# CANBed_M0.net
KiCad netlist of a schematic drawn in EAGLE
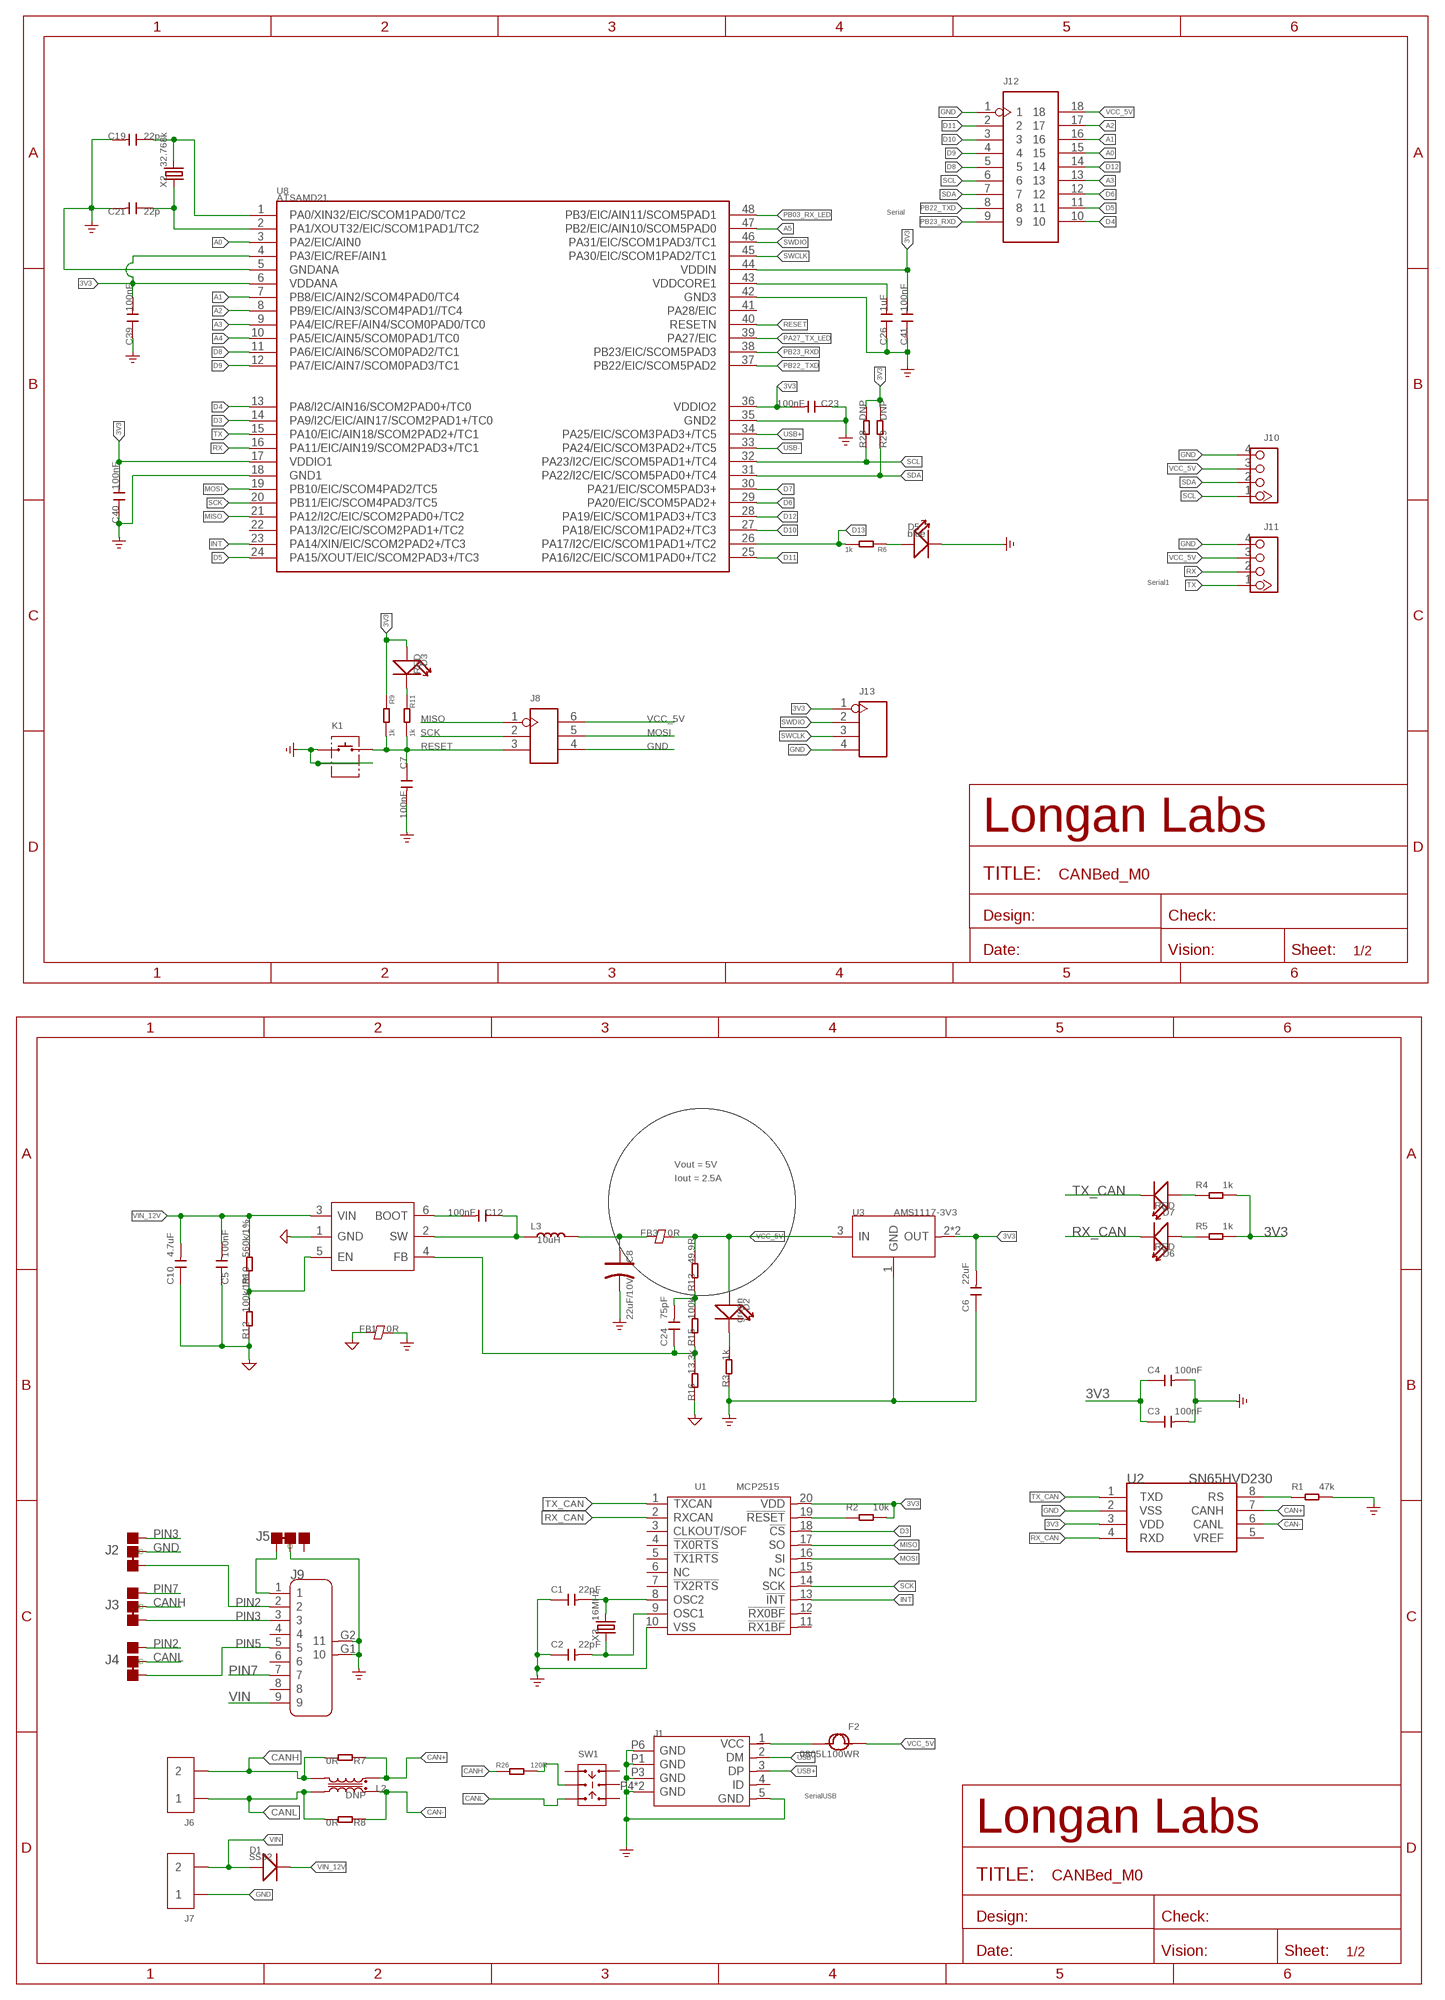
[diagram p0: schematic, sheet 1]

(export (version "E")
  (design (tool "Eeschema 10.0.6"))
  (components
    (comp (ref "C1")
      (value "22pF")
      (footprint "eagle-import:C0603")
      (libsource (lib "eagle-import") (part "CAP-0603"))
    )
    (comp (ref "C2")
      (value "22pF")
      (footprint "eagle-import:C0603")
      (libsource (lib "eagle-import") (part "CAP-0603"))
    )
    (comp (ref "C3")
      (value "100nF")
      (footprint "eagle-import:C0603")
      (libsource (lib "eagle-import") (part "CAP-0603"))
    )
    (comp (ref "C4")
      (value "100nF")
      (footprint "eagle-import:C0603")
      (libsource (lib "eagle-import") (part "CAP-0603"))
    )
    (comp (ref "C5")
      (value "100nF")
      (footprint "eagle-import:C0603")
      (libsource (lib "eagle-import") (part "CAP-0603"))
    )
    (comp (ref "C6")
      (value "22uF")
      (footprint "eagle-import:C1206")
      (libsource (lib "eagle-import") (part "CAP-1206"))
    )
    (comp (ref "C7")
      (value "100nF")
      (footprint "eagle-import:C0603")
      (libsource (lib "eagle-import") (part "CAP-0603"))
    )
    (comp (ref "C8")
      (value "22uF/10V")
      (footprint "eagle-import:AVX-B")
      (libsource (lib "eagle-import") (part "CAP-POLAR-AVX-B"))
    )
    (comp (ref "C10")
      (value "4.7uF")
      (footprint "eagle-import:C1206")
      (libsource (lib "eagle-import") (part "CAP-1206"))
    )
    (comp (ref "C12")
      (value "100nF")
      (footprint "eagle-import:C0603")
      (libsource (lib "eagle-import") (part "CAP-0603"))
    )
    (comp (ref "C19")
      (value "22p")
      (footprint "eagle-import:C0603")
      (libsource (lib "eagle-import") (part "CAP-0603"))
    )
    (comp (ref "C21")
      (value "22p")
      (footprint "eagle-import:C0603")
      (libsource (lib "eagle-import") (part "CAP-0603"))
    )
    (comp (ref "C23")
      (value "100nF")
      (footprint "eagle-import:C0603")
      (libsource (lib "eagle-import") (part "CAP-0603"))
    )
    (comp (ref "C24")
      (value "75pF")
      (footprint "eagle-import:C0603")
      (libsource (lib "eagle-import") (part "CAP-0603"))
    )
    (comp (ref "C26")
      (value "1uF")
      (footprint "eagle-import:C0603")
      (libsource (lib "eagle-import") (part "CAP-0603"))
    )
    (comp (ref "C39")
      (value "100nF")
      (footprint "eagle-import:C0603")
      (libsource (lib "eagle-import") (part "CAP-0603"))
    )
    (comp (ref "C40")
      (value "100nF")
      (footprint "eagle-import:C0603")
      (libsource (lib "eagle-import") (part "CAP-0603"))
    )
    (comp (ref "C41")
      (value "100nF")
      (footprint "eagle-import:C0603")
      (libsource (lib "eagle-import") (part "CAP-0603"))
    )
    (comp (ref "D1")
      (value "SS32")
      (footprint "eagle-import:DO-214AC")
      (libsource (lib "eagle-import") (part "DIODE'SMA'"))
    )
    (comp (ref "D2")
      (value "green")
      (footprint "eagle-import:LED-0603")
      (libsource (lib "eagle-import") (part "LED'0603'"))
    )
    (comp (ref "D3")
      (value "RED")
      (footprint "eagle-import:LED-0603")
      (libsource (lib "eagle-import") (part "LED'0603'"))
    )
    (comp (ref "D5")
      (value "blue")
      (footprint "eagle-import:LED-0603")
      (libsource (lib "eagle-import") (part "LED'0603'"))
    )
    (comp (ref "D6")
      (value "RED")
      (footprint "eagle-import:LED-0603")
      (libsource (lib "eagle-import") (part "LED'0603'"))
    )
    (comp (ref "D7")
      (value "RED")
      (footprint "eagle-import:LED-0603")
      (libsource (lib "eagle-import") (part "LED'0603'"))
    )
    (comp (ref "F2")
      (value "0805L100WR")
      (footprint "eagle-import:F0805")
      (libsource (lib "eagle-import") (part "FUSE0805"))
    )
    (comp (ref "FB1")
      (value "0R")
      (footprint "eagle-import:F0805")
      (libsource (lib "eagle-import") (part "FERRITE-BEAD-0805"))
    )
    (comp (ref "FB3")
      (value "0R")
      (footprint "eagle-import:F0805")
      (libsource (lib "eagle-import") (part "FERRITE-BEAD-0805"))
    )
    (comp (ref "J1")
      (value "MICRO-USB5+4P-320010050")
      (footprint "eagle-import:MICRO-USB5+5P-SMD-0.65-7.2X5.06MM")
      (libsource (lib "eagle-import") (part "MICRO-USB5+4P-320010050"))
    )
    (comp (ref "J2")
      (value "JUMPER-3P-SHORT")
      (footprint "eagle-import:3P-SMD-SHORT")
      (libsource (lib "eagle-import") (part "JUMPER-3P-SHORT"))
    )
    (comp (ref "J3")
      (value "JUMPER-3P-SHORT")
      (footprint "eagle-import:3P-SMD-SHORT")
      (libsource (lib "eagle-import") (part "JUMPER-3P-SHORT"))
    )
    (comp (ref "J4")
      (value "JUMPER-3P-SHORT")
      (footprint "eagle-import:3P-SMD-SHORT")
      (libsource (lib "eagle-import") (part "JUMPER-3P-SHORT"))
    )
    (comp (ref "J5")
      (value "JUMPER-3P-SHORT")
      (footprint "eagle-import:3P-SMD-SHORT")
      (libsource (lib "eagle-import") (part "JUMPER-3P-SHORT"))
    )
    (comp (ref "J6")
      (value "SCREW-TERMINAL-2P'5.08'")
      (footprint "eagle-import:H2-5.0-10.5X8.0MM")
      (libsource (lib "eagle-import") (part "SCREW-TERMINAL-2P'5.08'"))
    )
    (comp (ref "J7")
      (value "SCREW-TERMINAL-2P'5.08'")
      (footprint "eagle-import:H2-5.0-10.5X8.0MM")
      (libsource (lib "eagle-import") (part "SCREW-TERMINAL-2P'5.08'"))
    )
    (comp (ref "J8")
      (value "HEADER-2X3P-2.54")
      (footprint "eagle-import:H2X3-2.54")
      (libsource (lib "eagle-import") (part "HEADER-2X3P-2.54"))
    )
    (comp (ref "J9")
      (value "DB9'MEAL'")
      (footprint "eagle-import:DB9-MEAL")
      (libsource (lib "eagle-import") (part "DB9'MEAL'"))
    )
    (comp (ref "J10")
      (value "320110033")
      (footprint "eagle-import:HW4-2.0")
      (libsource (lib "eagle-import") (part "GROVE-CONNECTOR-DIP-2.0"))
    )
    (comp (ref "J11")
      (value "320110033")
      (footprint "eagle-import:HW4-2.0")
      (libsource (lib "eagle-import") (part "GROVE-CONNECTOR-DIP-2.0"))
    )
    (comp (ref "J12")
      (value "HEADER-2X9P-2.54")
      (footprint "eagle-import:H2X9-2.54")
      (libsource (lib "eagle-import") (part "HEADER-2X9P-2.54"))
    )
    (comp (ref "J13")
      (value "HEADER-4P-65/35MIL")
      (footprint "eagle-import:H4-2.54")
      (libsource (lib "eagle-import") (part "HEADER-4P-65/35MIL"))
    )
    (comp (ref "K1")
      (value "BUTTON-2+2P")
      (footprint "eagle-import:SW2+2P-7.7X2.75X3.95MM")
      (libsource (lib "eagle-import") (part "BUTTON-2+2P"))
    )
    (comp (ref "L2")
      (value "DNP")
      (footprint "eagle-import:INT4-0.85-2X1.25X1.2MM")
      (libsource (lib "eagle-import") (part "INDUCTOR-COMMON-MODE-SRF2012-900YA"))
    )
    (comp (ref "L3")
      (value "10uH")
      (footprint "eagle-import:INT2-SMD-6.6X7.1X3MM")
      (libsource (lib "eagle-import") (part "INDUCTOR-6.6X7.1"))
    )
    (comp (ref "R1")
      (value "47k")
      (footprint "eagle-import:R0603")
      (libsource (lib "eagle-import") (part "RES-0603"))
    )
    (comp (ref "R2")
      (value "10k")
      (footprint "eagle-import:R0603")
      (libsource (lib "eagle-import") (part "RES-0603"))
    )
    (comp (ref "R3")
      (value "1k")
      (footprint "eagle-import:R0603")
      (libsource (lib "eagle-import") (part "RES-0603"))
    )
    (comp (ref "R4")
      (value "1k")
      (footprint "eagle-import:R0603")
      (libsource (lib "eagle-import") (part "RES-0603"))
    )
    (comp (ref "R5")
      (value "1k")
      (footprint "eagle-import:R0603")
      (libsource (lib "eagle-import") (part "RES-0603"))
    )
    (comp (ref "R6")
      (value "1k")
      (footprint "eagle-import:R0603")
      (libsource (lib "eagle-import") (part "RES-0603"))
    )
    (comp (ref "R7")
      (value "0R")
      (footprint "eagle-import:R0603")
      (libsource (lib "eagle-import") (part "RES-0603"))
    )
    (comp (ref "R8")
      (value "0R")
      (footprint "eagle-import:R0603")
      (libsource (lib "eagle-import") (part "RES-0603"))
    )
    (comp (ref "R9")
      (value "1k")
      (footprint "eagle-import:R0603")
      (libsource (lib "eagle-import") (part "RES-0603"))
    )
    (comp (ref "R10")
      (value "560k/1%")
      (footprint "eagle-import:R0603")
      (libsource (lib "eagle-import") (part "RES-0603"))
    )
    (comp (ref "R11")
      (value "1k")
      (footprint "eagle-import:R0603")
      (libsource (lib "eagle-import") (part "RES-0603"))
    )
    (comp (ref "R12")
      (value "100k/1%")
      (footprint "eagle-import:R0603")
      (libsource (lib "eagle-import") (part "RES-0603"))
    )
    (comp (ref "R13")
      (value "49.9R")
      (footprint "eagle-import:R0603")
      (libsource (lib "eagle-import") (part "RES-0603"))
    )
    (comp (ref "R15")
      (value "100k")
      (footprint "eagle-import:R0603")
      (libsource (lib "eagle-import") (part "RES-0603"))
    )
    (comp (ref "R16")
      (value "13.3k")
      (footprint "eagle-import:R0603")
      (libsource (lib "eagle-import") (part "RES-0603"))
    )
    (comp (ref "R26")
      (value "120R")
      (footprint "eagle-import:R0603")
      (libsource (lib "eagle-import") (part "RES-0603"))
    )
    (comp (ref "R28")
      (value "DNP")
      (footprint "eagle-import:R0603")
      (libsource (lib "eagle-import") (part "RES-0603"))
    )
    (comp (ref "R29")
      (value "DNP")
      (footprint "eagle-import:R0603")
      (libsource (lib "eagle-import") (part "RES-0603"))
    )
    (comp (ref "SW1")
      (value "SWITCH-2CH-6P-311010004")
      (footprint "eagle-import:SW6-2.54-9.0X3.5X3.2+2.0MM")
      (libsource (lib "eagle-import") (part "SWITCH-2CH-6P-311010004"))
    )
    (comp (ref "U1")
      (value "MCP2515")
      (footprint "eagle-import:TSSOP20-0.65-6.5X4.4MM")
      (libsource (lib "eagle-import") (part "MCP2515'ST'"))
    )
    (comp (ref "U2")
      (value "SN65HVD230")
      (footprint "eagle-import:SOIC8-6.0")
      (libsource (lib "eagle-import") (part "MCP2551-SOIC8"))
    )
    (comp (ref "U3")
      (value "AMS1117-3V3")
      (footprint "eagle-import:SOT-223")
      (libsource (lib "eagle-import") (part "PMIC-CJ1117S"))
    )
    (comp (ref "U6")
      (value "PMIC-TPS54302")
      (footprint "eagle-import:SOT-23-6")
      (libsource (lib "eagle-import") (part "PMIC-TPS54302"))
    )
    (comp (ref "U8")
      (value "ATSAMD21")
      (footprint "eagle-import:TQFP48-0.5-7X7MM")
      (libsource (lib "eagle-import") (part "MCU-ATSAMD21-TQFP48"))
    )
    (comp (ref "X2")
      (value "32.768k")
      (footprint "eagle-import:X2-SMD-3.2X1.5X0.55MM")
      (libsource (lib "eagle-import") (part "CRYSTAL-2P-3215"))
    )
    (comp (ref "X3")
      (value "16MHz")
      (footprint "eagle-import:X4-SMD-3.2X2.5X0.7MM")
      (libsource (lib "eagle-import") (part "CRYSTAL-2P-3225"))
    )
  )
  (nets
    (net (code "1") (name "3V3") (class "Default")
      (node (ref "C23") (pin "2") (pinfunction "2_2") (pintype "passive"))
      (node (ref "C3") (pin "1") (pinfunction "1_1") (pintype "passive"))
      (node (ref "C39") (pin "2") (pinfunction "2_2") (pintype "passive"))
      (node (ref "C4") (pin "1") (pinfunction "1_1") (pintype "passive"))
      (node (ref "C40") (pin "2") (pinfunction "2_2") (pintype "passive"))
      (node (ref "C41") (pin "2") (pinfunction "2_2") (pintype "passive"))
      (node (ref "C6") (pin "2") (pinfunction "2_2") (pintype "passive"))
      (node (ref "D3") (pin "+") (pinfunction "+_+") (pintype "passive"))
      (node (ref "J13") (pin "1") (pinfunction "P$1_1") (pintype "bidirectional"))
      (node (ref "R2") (pin "2") (pinfunction "2_2") (pintype "passive"))
      (node (ref "R28") (pin "2") (pinfunction "2_2") (pintype "passive"))
      (node (ref "R29") (pin "1") (pinfunction "1_1") (pintype "passive"))
      (node (ref "R4") (pin "2") (pinfunction "2_2") (pintype "passive"))
      (node (ref "R5") (pin "2") (pinfunction "2_2") (pintype "passive"))
      (node (ref "R9") (pin "1") (pinfunction "1_1") (pintype "passive"))
      (node (ref "U1") (pin "20") (pinfunction "VDD_20") (pintype "bidirectional"))
      (node (ref "U2") (pin "3") (pinfunction "VDD_3") (pintype "bidirectional"))
      (node (ref "U3") (pin "2") (pinfunction "OUT_2") (pintype "bidirectional"))
      (node (ref "U3") (pin "TER") (pinfunction "OUT_TER") (pintype "bidirectional"))
      (node (ref "U8") (pin "17") (pinfunction "VDDIO1_17") (pintype "power_in"))
      (node (ref "U8") (pin "36") (pinfunction "VDDIO2_36") (pintype "power_in"))
      (node (ref "U8") (pin "4") (pinfunction "PA3/EIC/REF/AIN1_4") (pintype "bidirectional"))
      (node (ref "U8") (pin "44") (pinfunction "VDDIN_44") (pintype "power_in"))
      (node (ref "U8") (pin "6") (pinfunction "VDDANA_6") (pintype "power_in"))
    )
    (net (code "2") (name "A0") (class "Default")
      (node (ref "J12") (pin "15") (pinfunction "15_15") (pintype "bidirectional"))
      (node (ref "U8") (pin "3") (pinfunction "PA2/EIC/AIN0_3") (pintype "bidirectional"))
    )
    (net (code "3") (name "A1") (class "Default")
      (node (ref "J12") (pin "16") (pinfunction "16_16") (pintype "bidirectional"))
      (node (ref "U8") (pin "7") (pinfunction "PB8/EIC/AIN2/SCOM4PAD0/TC4_7") (pintype "bidirectional"))
    )
    (net (code "4") (name "A2") (class "Default")
      (node (ref "J12") (pin "17") (pinfunction "17_17") (pintype "bidirectional"))
      (node (ref "U8") (pin "8") (pinfunction "PB9/EIC/AIN3/SCOM4PAD1//TC4_8") (pintype "bidirectional"))
    )
    (net (code "5") (name "A3") (class "Default")
      (node (ref "J12") (pin "13") (pinfunction "13_13") (pintype "bidirectional"))
      (node (ref "U8") (pin "9") (pinfunction "PA4/EIC/REF/AIN4/SCOM0PAD0/TC0_9") (pintype "bidirectional"))
    )
    (net (code "6") (name "A4") (class "Default")
      (node (ref "U8") (pin "10") (pinfunction "PA5/EIC/AIN5/SCOM0PAD1/TC0_10") (pintype "bidirectional"))
    )
    (net (code "7") (name "A5") (class "Default")
      (node (ref "U8") (pin "47") (pinfunction "PB2/EIC/AIN10/SCOM5PAD0_47") (pintype "bidirectional"))
    )
    (net (code "8") (name "AGND") (class "Default")
      (node (ref "C10") (pin "1") (pinfunction "1_1") (pintype "passive"))
      (node (ref "C5") (pin "1") (pinfunction "1_1") (pintype "passive"))
      (node (ref "FB1") (pin "1") (pinfunction "1_1") (pintype "bidirectional"))
      (node (ref "R12") (pin "1") (pinfunction "1_1") (pintype "passive"))
      (node (ref "R16") (pin "1") (pinfunction "1_1") (pintype "passive"))
      (node (ref "U6") (pin "1") (pinfunction "GND_1") (pintype "bidirectional"))
    )
    (net (code "9") (name "CAN+") (class "Default")
      (node (ref "L2") (pin "4") (pinfunction "4_4") (pintype "bidirectional"))
      (node (ref "R7") (pin "1") (pinfunction "1_1") (pintype "passive"))
      (node (ref "U2") (pin "7") (pinfunction "CANH_7") (pintype "bidirectional"))
    )
    (net (code "10") (name "CAN-") (class "Default")
      (node (ref "L2") (pin "1") (pinfunction "1_1") (pintype "bidirectional"))
      (node (ref "R8") (pin "1") (pinfunction "1_1") (pintype "passive"))
      (node (ref "U2") (pin "6") (pinfunction "CANL_6") (pintype "bidirectional"))
    )
    (net (code "11") (name "CANH") (class "Default")
      (node (ref "J3") (pin "MM") (pinfunction "C_MM") (pintype "bidirectional"))
      (node (ref "J6") (pin "2") (pinfunction "2_2") (pintype "bidirectional"))
      (node (ref "L2") (pin "3") (pinfunction "3_3") (pintype "bidirectional"))
      (node (ref "R26") (pin "1") (pinfunction "1_1") (pintype "passive"))
      (node (ref "R7") (pin "2") (pinfunction "2_2") (pintype "passive"))
    )
    (net (code "12") (name "CANL") (class "Default")
      (node (ref "J4") (pin "MM") (pinfunction "C_MM") (pintype "bidirectional"))
      (node (ref "J6") (pin "1") (pinfunction "1_1") (pintype "bidirectional"))
      (node (ref "L2") (pin "2") (pinfunction "2_2") (pintype "bidirectional"))
      (node (ref "R8") (pin "2") (pinfunction "2_2") (pintype "passive"))
      (node (ref "SW1") (pin "CH1B") (pinfunction "CH1B_CH1B") (pintype "bidirectional"))
    )
    (net (code "13") (name "D3") (class "Default")
      (node (ref "U1") (pin "18") (pinfunction "~{CS}_18") (pintype "bidirectional"))
      (node (ref "U8") (pin "14") (pinfunction "PA9/I2C/EIC/AIN17/SCOM2PAD1+/TC0_14") (pintype "bidirectional"))
    )
    (net (code "14") (name "D4") (class "Default")
      (node (ref "J12") (pin "10") (pinfunction "10_10") (pintype "bidirectional"))
      (node (ref "U8") (pin "13") (pinfunction "PA8/I2C/AIN16/SCOM2PAD0+/TC0_13") (pintype "bidirectional"))
    )
    (net (code "15") (name "D5") (class "Default")
      (node (ref "J12") (pin "11") (pinfunction "11_11") (pintype "bidirectional"))
      (node (ref "U8") (pin "24") (pinfunction "PA15/XOUT/EIC/SCOM2PAD3+/TC3_24") (pintype "bidirectional"))
    )
    (net (code "16") (name "D6") (class "Default")
      (node (ref "J12") (pin "12") (pinfunction "12_12") (pintype "bidirectional"))
      (node (ref "U8") (pin "29") (pinfunction "PA20/EIC/SCOM5PAD2+_29") (pintype "bidirectional"))
    )
    (net (code "17") (name "D7") (class "Default")
      (node (ref "U8") (pin "30") (pinfunction "PA21/EIC/SCOM5PAD3+_30") (pintype "bidirectional"))
    )
    (net (code "18") (name "D8") (class "Default")
      (node (ref "J12") (pin "5") (pinfunction "5_5") (pintype "bidirectional"))
      (node (ref "U8") (pin "11") (pinfunction "PA6/EIC/AIN6/SCOM0PAD2/TC1_11") (pintype "bidirectional"))
    )
    (net (code "19") (name "D9") (class "Default")
      (node (ref "J12") (pin "4") (pinfunction "4_4") (pintype "bidirectional"))
      (node (ref "U8") (pin "12") (pinfunction "PA7/EIC/AIN7/SCOM0PAD3/TC1_12") (pintype "bidirectional"))
    )
    (net (code "20") (name "D10") (class "Default")
      (node (ref "J12") (pin "3") (pinfunction "3_3") (pintype "bidirectional"))
      (node (ref "U8") (pin "27") (pinfunction "PA18/EIC/SCOM1PAD2+/TC3_27") (pintype "bidirectional"))
    )
    (net (code "21") (name "D11") (class "Default")
      (node (ref "J12") (pin "2") (pinfunction "2_2") (pintype "bidirectional"))
      (node (ref "U8") (pin "25") (pinfunction "PA16/I2C/EIC/SCOM1PAD0+/TC2_25") (pintype "bidirectional"))
    )
    (net (code "22") (name "D12") (class "Default")
      (node (ref "J12") (pin "14") (pinfunction "14_14") (pintype "bidirectional"))
      (node (ref "U8") (pin "28") (pinfunction "PA19/EIC/SCOM1PAD3+/TC3_28") (pintype "bidirectional"))
    )
    (net (code "23") (name "D13") (class "Default")
      (node (ref "R6") (pin "2") (pinfunction "2_2") (pintype "passive"))
      (node (ref "U8") (pin "26") (pinfunction "PA17/I2C/EIC/SCOM1PAD1+/TC2_26") (pintype "bidirectional"))
    )
    (net (code "24") (name "GND") (class "Default")
      (node (ref "C1") (pin "1") (pinfunction "1_1") (pintype "passive"))
      (node (ref "C19") (pin "2") (pinfunction "2_2") (pintype "passive"))
      (node (ref "C2") (pin "1") (pinfunction "1_1") (pintype "passive"))
      (node (ref "C21") (pin "2") (pinfunction "2_2") (pintype "passive"))
      (node (ref "C23") (pin "1") (pinfunction "1_1") (pintype "passive"))
      (node (ref "C26") (pin "1") (pinfunction "1_1") (pintype "passive"))
      (node (ref "C3") (pin "2") (pinfunction "2_2") (pintype "passive"))
      (node (ref "C39") (pin "1") (pinfunction "1_1") (pintype "passive"))
      (node (ref "C4") (pin "2") (pinfunction "2_2") (pintype "passive"))
      (node (ref "C40") (pin "1") (pinfunction "1_1") (pintype "passive"))
      (node (ref "C41") (pin "1") (pinfunction "1_1") (pintype "passive"))
      (node (ref "C6") (pin "1") (pinfunction "1_1") (pintype "passive"))
      (node (ref "C7") (pin "2") (pinfunction "2_2") (pintype "passive"))
      (node (ref "C8") (pin "-") (pinfunction "-_-") (pintype "passive"))
      (node (ref "D5") (pin "-") (pinfunction "-_-") (pintype "passive"))
      (node (ref "FB1") (pin "2") (pinfunction "2_2") (pintype "bidirectional"))
      (node (ref "J1") (pin "5") (pinfunction "GND_5") (pintype "bidirectional"))
      (node (ref "J1") (pin "P1") (pinfunction "GND_P1") (pintype "bidirectional"))
      (node (ref "J1") (pin "P3") (pinfunction "GND_P3") (pintype "bidirectional"))
      (node (ref "J1") (pin "P4") (pinfunction "GND_P4") (pintype "bidirectional"))
      (node (ref "J1") (pin "P5") (pinfunction "GND_P5") (pintype "bidirectional"))
      (node (ref "J1") (pin "P6") (pinfunction "GND_P6") (pintype "bidirectional"))
      (node (ref "J10") (pin "4") (pinfunction "4_4") (pintype "bidirectional"))
      (node (ref "J11") (pin "4") (pinfunction "4_4") (pintype "bidirectional"))
      (node (ref "J12") (pin "1") (pinfunction "1_1") (pintype "bidirectional"))
      (node (ref "J13") (pin "4") (pinfunction "P$4_4") (pintype "bidirectional"))
      (node (ref "J2") (pin "MM") (pinfunction "C_MM") (pintype "bidirectional"))
      (node (ref "J5") (pin "MM") (pinfunction "C_MM") (pintype "bidirectional"))
      (node (ref "J7") (pin "1") (pinfunction "1_1") (pintype "bidirectional"))
      (node (ref "J8") (pin "4") (pinfunction "4_4") (pintype "bidirectional"))
      (node (ref "J9") (pin "G1") (pinfunction "10_G1") (pintype "bidirectional"))
      (node (ref "J9") (pin "G2") (pinfunction "11_G2") (pintype "bidirectional"))
      (node (ref "K1") (pin "1") (pinfunction "1_1") (pintype "bidirectional"))
      (node (ref "K1") (pin "S1") (pinfunction "S1_S1") (pintype "bidirectional"))
      (node (ref "K1") (pin "S2") (pinfunction "S2_S2") (pintype "bidirectional"))
      (node (ref "R1") (pin "2") (pinfunction "2_2") (pintype "passive"))
      (node (ref "R3") (pin "1") (pinfunction "1_1") (pintype "passive"))
      (node (ref "U1") (pin "10") (pinfunction "VSS_10") (pintype "bidirectional"))
      (node (ref "U2") (pin "2") (pinfunction "VSS_2") (pintype "bidirectional"))
      (node (ref "U3") (pin "1") (pinfunction "GND_1") (pintype "bidirectional"))
      (node (ref "U8") (pin "18") (pinfunction "GND1_18") (pintype "power_in"))
      (node (ref "U8") (pin "35") (pinfunction "GND2_35") (pintype "power_in"))
      (node (ref "U8") (pin "42") (pinfunction "GND3_42") (pintype "power_in"))
      (node (ref "U8") (pin "5") (pinfunction "GNDANA_5") (pintype "power_in"))
    )
    (net (code "25") (name "INT") (class "Default")
      (node (ref "U1") (pin "13") (pinfunction "~{INT}_13") (pintype "bidirectional"))
      (node (ref "U8") (pin "23") (pinfunction "PA14/XIN/EIC/SCOM2PAD2+/TC3_23") (pintype "bidirectional"))
    )
    (net (code "26") (name "MISO") (class "Default")
      (node (ref "J8") (pin "1") (pinfunction "1_1") (pintype "bidirectional"))
      (node (ref "U1") (pin "17") (pinfunction "SO_17") (pintype "bidirectional"))
      (node (ref "U8") (pin "21") (pinfunction "PA12/I2C/EIC/SCOM2PAD0+/TC2_21") (pintype "bidirectional"))
    )
    (net (code "27") (name "MOSI") (class "Default")
      (node (ref "J8") (pin "5") (pinfunction "5_5") (pintype "bidirectional"))
      (node (ref "U1") (pin "16") (pinfunction "SI_16") (pintype "bidirectional"))
      (node (ref "U8") (pin "19") (pinfunction "PB10/EIC/SCOM4PAD2/TC5_19") (pintype "bidirectional"))
    )
    (net (code "28") (name "Net-(C8-Pad+)") (class "Default")
      (node (ref "C8") (pin "+") (pinfunction "+_+") (pintype "passive"))
      (node (ref "FB3") (pin "1") (pinfunction "1_1") (pintype "bidirectional"))
      (node (ref "L3") (pin "2") (pinfunction "2_2") (pintype "passive"))
    )
    (net (code "29") (name "Net-(C24-Pad2)") (class "Default")
      (node (ref "C24") (pin "2") (pinfunction "2_2") (pintype "passive"))
      (node (ref "R13") (pin "1") (pinfunction "1_1") (pintype "passive"))
      (node (ref "R15") (pin "2") (pinfunction "2_2") (pintype "passive"))
    )
    (net (code "30") (name "Net-(D2-Pad-)") (class "Default")
      (node (ref "D2") (pin "-") (pinfunction "-_-") (pintype "passive"))
      (node (ref "R3") (pin "2") (pinfunction "2_2") (pintype "passive"))
    )
    (net (code "31") (name "Net-(D3-Pad-)") (class "Default")
      (node (ref "D3") (pin "-") (pinfunction "-_-") (pintype "passive"))
      (node (ref "R11") (pin "1") (pinfunction "1_1") (pintype "passive"))
    )
    (net (code "32") (name "Net-(D5-Pad+)") (class "Default")
      (node (ref "D5") (pin "+") (pinfunction "+_+") (pintype "passive"))
      (node (ref "R6") (pin "1") (pinfunction "1_1") (pintype "passive"))
    )
    (net (code "33") (name "Net-(D6-Pad+)") (class "Default")
      (node (ref "D6") (pin "+") (pinfunction "+_+") (pintype "passive"))
      (node (ref "R5") (pin "1") (pinfunction "1_1") (pintype "passive"))
    )
    (net (code "34") (name "Net-(D7-Pad+)") (class "Default")
      (node (ref "D7") (pin "+") (pinfunction "+_+") (pintype "passive"))
      (node (ref "R4") (pin "1") (pinfunction "1_1") (pintype "passive"))
    )
    (net (code "35") (name "Net-(J1-VCC)") (class "Default")
      (node (ref "F2") (pin "2") (pinfunction "2_2") (pintype "bidirectional"))
      (node (ref "J1") (pin "1") (pinfunction "VCC_1") (pintype "bidirectional"))
    )
    (net (code "36") (name "Net-(J5-L)") (class "Default")
      (node (ref "J5") (pin "11") (pinfunction "L_11") (pintype "bidirectional"))
      (node (ref "J9") (pin "1") (pinfunction "1_1") (pintype "bidirectional"))
    )
    (net (code "37") (name "Net-(R26-Pad2)") (class "Default")
      (node (ref "R26") (pin "2") (pinfunction "2_2") (pintype "passive"))
      (node (ref "SW1") (pin "COM1") (pinfunction "COM1_COM1") (pintype "bidirectional"))
    )
    (net (code "38") (name "Net-(U1-OSC1)") (class "Default")
      (node (ref "C2") (pin "2") (pinfunction "2_2") (pintype "passive"))
      (node (ref "U1") (pin "9") (pinfunction "OSC1_9") (pintype "bidirectional"))
      (node (ref "X3") (pin "1") (pinfunction "1_1") (pintype "passive"))
    )
    (net (code "39") (name "Net-(U1-OSC2)") (class "Default")
      (node (ref "C1") (pin "2") (pinfunction "2_2") (pintype "passive"))
      (node (ref "U1") (pin "8") (pinfunction "OSC2_8") (pintype "bidirectional"))
      (node (ref "X3") (pin "3") (pinfunction "2_3") (pintype "passive"))
    )
    (net (code "40") (name "Net-(U1-~{RESET})") (class "Default")
      (node (ref "R2") (pin "1") (pinfunction "1_1") (pintype "passive"))
      (node (ref "U1") (pin "19") (pinfunction "~{RESET}_19") (pintype "bidirectional"))
    )
    (net (code "41") (name "Net-(U2-RS)") (class "Default")
      (node (ref "R1") (pin "1") (pinfunction "1_1") (pintype "passive"))
      (node (ref "U2") (pin "8") (pinfunction "RS_8") (pintype "bidirectional"))
    )
    (net (code "42") (name "Net-(U6-BOOT)") (class "Default")
      (node (ref "C12") (pin "2") (pinfunction "2_2") (pintype "passive"))
      (node (ref "U6") (pin "6") (pinfunction "BOOT_6") (pintype "bidirectional"))
    )
    (net (code "43") (name "Net-(U6-EN)") (class "Default")
      (node (ref "R10") (pin "1") (pinfunction "1_1") (pintype "passive"))
      (node (ref "R12") (pin "2") (pinfunction "2_2") (pintype "passive"))
      (node (ref "U6") (pin "5") (pinfunction "EN_5") (pintype "bidirectional"))
    )
    (net (code "44") (name "Net-(U6-FB)") (class "Default")
      (node (ref "C24") (pin "1") (pinfunction "1_1") (pintype "passive"))
      (node (ref "R15") (pin "1") (pinfunction "1_1") (pintype "passive"))
      (node (ref "R16") (pin "2") (pinfunction "2_2") (pintype "passive"))
      (node (ref "U6") (pin "4") (pinfunction "FB_4") (pintype "bidirectional"))
    )
    (net (code "45") (name "Net-(U6-SW)") (class "Default")
      (node (ref "C12") (pin "1") (pinfunction "1_1") (pintype "passive"))
      (node (ref "L3") (pin "1") (pinfunction "1_1") (pintype "passive"))
      (node (ref "U6") (pin "2") (pinfunction "SW_2") (pintype "bidirectional"))
    )
    (net (code "46") (name "Net-(U8-PA0{slash}XIN32{slash}EIC{slash}SCOM1PAD0{slash}TC2)") (class "Default")
      (node (ref "C19") (pin "1") (pinfunction "1_1") (pintype "passive"))
      (node (ref "U8") (pin "1") (pinfunction "PA0/XIN32/EIC/SCOM1PAD0/TC2_1") (pintype "bidirectional"))
      (node (ref "X2") (pin "2") (pinfunction "2_2") (pintype "passive"))
    )
    (net (code "47") (name "Net-(U8-PA1{slash}XOUT32{slash}EIC{slash}SCOM1PAD1{slash}TC2)") (class "Default")
      (node (ref "C21") (pin "1") (pinfunction "1_1") (pintype "passive"))
      (node (ref "U8") (pin "2") (pinfunction "PA1/XOUT32/EIC/SCOM1PAD1/TC2_2") (pintype "bidirectional"))
      (node (ref "X2") (pin "1") (pinfunction "1_1") (pintype "passive"))
    )
    (net (code "48") (name "Net-(U8-VDDCORE1)") (class "Default")
      (node (ref "C26") (pin "2") (pinfunction "2_2") (pintype "passive"))
      (node (ref "U8") (pin "43") (pinfunction "VDDCORE1_43") (pintype "input"))
    )
    (net (code "49") (name "PA27_TX_LED") (class "Default")
      (node (ref "U8") (pin "39") (pinfunction "PA27/EIC_39") (pintype "bidirectional"))
    )
    (net (code "50") (name "PB03_RX_LED") (class "Default")
      (node (ref "U8") (pin "48") (pinfunction "PB3/EIC/AIN11/SCOM5PAD1_48") (pintype "bidirectional"))
    )
    (net (code "51") (name "PB22_TXD") (class "Default")
      (node (ref "J12") (pin "8") (pinfunction "8_8") (pintype "bidirectional"))
      (node (ref "U8") (pin "37") (pinfunction "PB22/EIC/SCOM5PAD2_37") (pintype "bidirectional"))
    )
    (net (code "52") (name "PB23_RXD") (class "Default")
      (node (ref "J12") (pin "9") (pinfunction "9_9") (pintype "bidirectional"))
      (node (ref "U8") (pin "38") (pinfunction "PB23/EIC/SCOM5PAD3_38") (pintype "bidirectional"))
    )
    (net (code "53") (name "PIN2") (class "Default")
      (node (ref "J2") (pin "11") (pinfunction "L_11") (pintype "bidirectional"))
      (node (ref "J4") (pin "00") (pinfunction "R_00") (pintype "bidirectional"))
      (node (ref "J9") (pin "2") (pinfunction "2_2") (pintype "bidirectional"))
    )
    (net (code "54") (name "PIN3") (class "Default")
      (node (ref "J2") (pin "00") (pinfunction "R_00") (pintype "bidirectional"))
      (node (ref "J3") (pin "11") (pinfunction "L_11") (pintype "bidirectional"))
      (node (ref "J9") (pin "3") (pinfunction "3_3") (pintype "bidirectional"))
    )
    (net (code "55") (name "PIN5") (class "Default")
      (node (ref "J4") (pin "11") (pinfunction "L_11") (pintype "bidirectional"))
      (node (ref "J9") (pin "5") (pinfunction "5_5") (pintype "bidirectional"))
    )
    (net (code "56") (name "PIN7") (class "Default")
      (node (ref "J3") (pin "00") (pinfunction "R_00") (pintype "bidirectional"))
      (node (ref "J9") (pin "7") (pinfunction "7_7") (pintype "bidirectional"))
    )
    (net (code "57") (name "RESET") (class "Default")
      (node (ref "C7") (pin "1") (pinfunction "1_1") (pintype "passive"))
      (node (ref "J8") (pin "3") (pinfunction "3_3") (pintype "bidirectional"))
      (node (ref "K1") (pin "2") (pinfunction "2_2") (pintype "bidirectional"))
      (node (ref "R11") (pin "2") (pinfunction "2_2") (pintype "passive"))
      (node (ref "R9") (pin "2") (pinfunction "2_2") (pintype "passive"))
      (node (ref "U8") (pin "40") (pinfunction "RESETN_40") (pintype "bidirectional"))
    )
    (net (code "58") (name "RX") (class "Default")
      (node (ref "J11") (pin "2") (pinfunction "2_2") (pintype "bidirectional"))
      (node (ref "U8") (pin "16") (pinfunction "PA11/EIC/AIN19/SCOM2PAD3+/TC1_16") (pintype "bidirectional"))
    )
    (net (code "59") (name "RX_CAN") (class "Default")
      (node (ref "D6") (pin "-") (pinfunction "-_-") (pintype "passive"))
      (node (ref "U1") (pin "2") (pinfunction "RXCAN_2") (pintype "bidirectional"))
      (node (ref "U2") (pin "4") (pinfunction "RXD_4") (pintype "bidirectional"))
    )
    (net (code "60") (name "SCK") (class "Default")
      (node (ref "J8") (pin "2") (pinfunction "2_2") (pintype "bidirectional"))
      (node (ref "U1") (pin "14") (pinfunction "SCK_14") (pintype "bidirectional"))
      (node (ref "U8") (pin "20") (pinfunction "PB11/EIC/SCOM4PAD3/TC5_20") (pintype "bidirectional"))
    )
    (net (code "61") (name "SCL") (class "Default")
      (node (ref "J10") (pin "1") (pinfunction "1_1") (pintype "bidirectional"))
      (node (ref "J12") (pin "6") (pinfunction "6_6") (pintype "bidirectional"))
      (node (ref "R28") (pin "1") (pinfunction "1_1") (pintype "passive"))
      (node (ref "U8") (pin "32") (pinfunction "PA23/I2C/EIC/SCOM5PAD1+/TC4_32") (pintype "bidirectional"))
    )
    (net (code "62") (name "SDA") (class "Default")
      (node (ref "J10") (pin "2") (pinfunction "2_2") (pintype "bidirectional"))
      (node (ref "J12") (pin "7") (pinfunction "7_7") (pintype "bidirectional"))
      (node (ref "R29") (pin "2") (pinfunction "2_2") (pintype "passive"))
      (node (ref "U8") (pin "31") (pinfunction "PA22/I2C/EIC/SCOM5PAD0+/TC4_31") (pintype "bidirectional"))
    )
    (net (code "63") (name "SWCLK") (class "Default")
      (node (ref "J13") (pin "3") (pinfunction "P$3_3") (pintype "bidirectional"))
      (node (ref "U8") (pin "45") (pinfunction "PA30/EIC/SCOM1PAD2/TC1_45") (pintype "bidirectional"))
    )
    (net (code "64") (name "SWDIO") (class "Default")
      (node (ref "J13") (pin "2") (pinfunction "P$2_2") (pintype "bidirectional"))
      (node (ref "U8") (pin "46") (pinfunction "PA31/EIC/SCOM1PAD3/TC1_46") (pintype "bidirectional"))
    )
    (net (code "65") (name "TX") (class "Default")
      (node (ref "J11") (pin "1") (pinfunction "1_1") (pintype "bidirectional"))
      (node (ref "U8") (pin "15") (pinfunction "PA10/EIC/AIN18/SCOM2PAD2+/TC1_15") (pintype "bidirectional"))
    )
    (net (code "66") (name "TX_CAN") (class "Default")
      (node (ref "D7") (pin "-") (pinfunction "-_-") (pintype "passive"))
      (node (ref "U1") (pin "1") (pinfunction "TXCAN_1") (pintype "bidirectional"))
      (node (ref "U2") (pin "1") (pinfunction "TXD_1") (pintype "bidirectional"))
    )
    (net (code "67") (name "USB+") (class "Default")
      (node (ref "J1") (pin "3") (pinfunction "DP_3") (pintype "bidirectional"))
      (node (ref "U8") (pin "34") (pinfunction "PA25/EIC/SCOM3PAD3+/TC5_34") (pintype "bidirectional"))
    )
    (net (code "68") (name "USB-") (class "Default")
      (node (ref "J1") (pin "2") (pinfunction "DM_2") (pintype "bidirectional"))
      (node (ref "U8") (pin "33") (pinfunction "PA24/EIC/SCOM3PAD2+/TC5_33") (pintype "bidirectional"))
    )
    (net (code "69") (name "VCC_5V") (class "Default")
      (node (ref "D2") (pin "+") (pinfunction "+_+") (pintype "passive"))
      (node (ref "F2") (pin "1") (pinfunction "1_1") (pintype "bidirectional"))
      (node (ref "FB3") (pin "2") (pinfunction "2_2") (pintype "bidirectional"))
      (node (ref "J10") (pin "3") (pinfunction "3_3") (pintype "bidirectional"))
      (node (ref "J11") (pin "3") (pinfunction "3_3") (pintype "bidirectional"))
      (node (ref "J12") (pin "18") (pinfunction "18_18") (pintype "bidirectional"))
      (node (ref "J8") (pin "6") (pinfunction "6_6") (pintype "bidirectional"))
      (node (ref "R13") (pin "2") (pinfunction "2_2") (pintype "passive"))
      (node (ref "U3") (pin "3") (pinfunction "IN_3") (pintype "bidirectional"))
    )
    (net (code "70") (name "VIN") (class "Default")
      (node (ref "D1") (pin "1") (pinfunction "+_1") (pintype "passive"))
      (node (ref "J7") (pin "2") (pinfunction "2_2") (pintype "bidirectional"))
      (node (ref "J9") (pin "9") (pinfunction "9_9") (pintype "bidirectional"))
    )
    (net (code "71") (name "VIN_12V") (class "Default")
      (node (ref "C10") (pin "2") (pinfunction "2_2") (pintype "passive"))
      (node (ref "C5") (pin "2") (pinfunction "2_2") (pintype "passive"))
      (node (ref "D1") (pin "2") (pinfunction "-_2") (pintype "passive"))
      (node (ref "R10") (pin "2") (pinfunction "2_2") (pintype "passive"))
      (node (ref "U6") (pin "3") (pinfunction "VIN_3") (pintype "bidirectional"))
    )
    (net (code "72") (name "unconnected-(J1-ID-Pad4)") (class "Default")
      (node (ref "J1") (pin "4") (pinfunction "ID_4") (pintype "bidirectional"))
    )
    (net (code "73") (name "unconnected-(J5-R-Pad00)") (class "Default")
      (node (ref "J5") (pin "00") (pinfunction "R_00") (pintype "bidirectional"))
    )
    (net (code "74") (name "unconnected-(J9-Pad4)") (class "Default")
      (node (ref "J9") (pin "4") (pinfunction "4_4") (pintype "bidirectional"))
    )
    (net (code "75") (name "unconnected-(J9-Pad6)") (class "Default")
      (node (ref "J9") (pin "6") (pinfunction "6_6") (pintype "bidirectional"))
    )
    (net (code "76") (name "unconnected-(J9-Pad8)") (class "Default")
      (node (ref "J9") (pin "8") (pinfunction "8_8") (pintype "bidirectional"))
    )
    (net (code "77") (name "unconnected-(SW1-PadCH1A)") (class "Default")
      (node (ref "SW1") (pin "CH1A") (pinfunction "CH1A_CH1A") (pintype "bidirectional"))
    )
    (net (code "78") (name "unconnected-(SW1-PadCH2A)") (class "Default")
      (node (ref "SW1") (pin "CH2A") (pinfunction "CH2A_CH2A") (pintype "bidirectional"))
    )
    (net (code "79") (name "unconnected-(SW1-PadCH2B)") (class "Default")
      (node (ref "SW1") (pin "CH2B") (pinfunction "CH2B_CH2B") (pintype "bidirectional"))
    )
    (net (code "80") (name "unconnected-(SW1-PadCOM2)") (class "Default")
      (node (ref "SW1") (pin "COM2") (pinfunction "COM2_COM2") (pintype "bidirectional"))
    )
    (net (code "81") (name "unconnected-(U1-CLKOUT{slash}SOF-Pad3)") (class "Default")
      (node (ref "U1") (pin "3") (pinfunction "CLKOUT/SOF_3") (pintype "bidirectional"))
    )
    (net (code "82") (name "unconnected-(U1-NC-Pad6)") (class "Default")
      (node (ref "U1") (pin "6") (pinfunction "NC_6") (pintype "bidirectional"))
    )
    (net (code "83") (name "unconnected-(U1-NC-Pad15)") (class "Default")
      (node (ref "U1") (pin "15") (pinfunction "NC_15") (pintype "bidirectional"))
    )
    (net (code "84") (name "unconnected-(U1-~{RX0BF}-Pad12)") (class "Default")
      (node (ref "U1") (pin "12") (pinfunction "~{RX0BF}_12") (pintype "bidirectional"))
    )
    (net (code "85") (name "unconnected-(U1-~{RX1BF}-Pad11)") (class "Default")
      (node (ref "U1") (pin "11") (pinfunction "~{RX1BF}_11") (pintype "bidirectional"))
    )
    (net (code "86") (name "unconnected-(U1-~{TX0RTS}-Pad4)") (class "Default")
      (node (ref "U1") (pin "4") (pinfunction "~{TX0RTS}_4") (pintype "bidirectional"))
    )
    (net (code "87") (name "unconnected-(U1-~{TX1RTS}-Pad5)") (class "Default")
      (node (ref "U1") (pin "5") (pinfunction "~{TX1RTS}_5") (pintype "bidirectional"))
    )
    (net (code "88") (name "unconnected-(U1-~{TX2RTS}-Pad7)") (class "Default")
      (node (ref "U1") (pin "7") (pinfunction "~{TX2RTS}_7") (pintype "bidirectional"))
    )
    (net (code "89") (name "unconnected-(U2-VREF-Pad5)") (class "Default")
      (node (ref "U2") (pin "5") (pinfunction "VREF_5") (pintype "bidirectional"))
    )
    (net (code "90") (name "unconnected-(U8-PA13{slash}I2C{slash}EIC{slash}SCOM2PAD1+{slash}TC2-Pad22)") (class "Default")
      (node (ref "U8") (pin "22") (pinfunction "PA13/I2C/EIC/SCOM2PAD1+/TC2_22") (pintype "bidirectional"))
    )
    (net (code "91") (name "unconnected-(U8-PA28{slash}EIC-Pad41)") (class "Default")
      (node (ref "U8") (pin "41") (pinfunction "PA28/EIC_41") (pintype "bidirectional"))
    )
  )
)
